# DDS_channel.net
KiCad netlist of a schematic drawn in Altium Designer
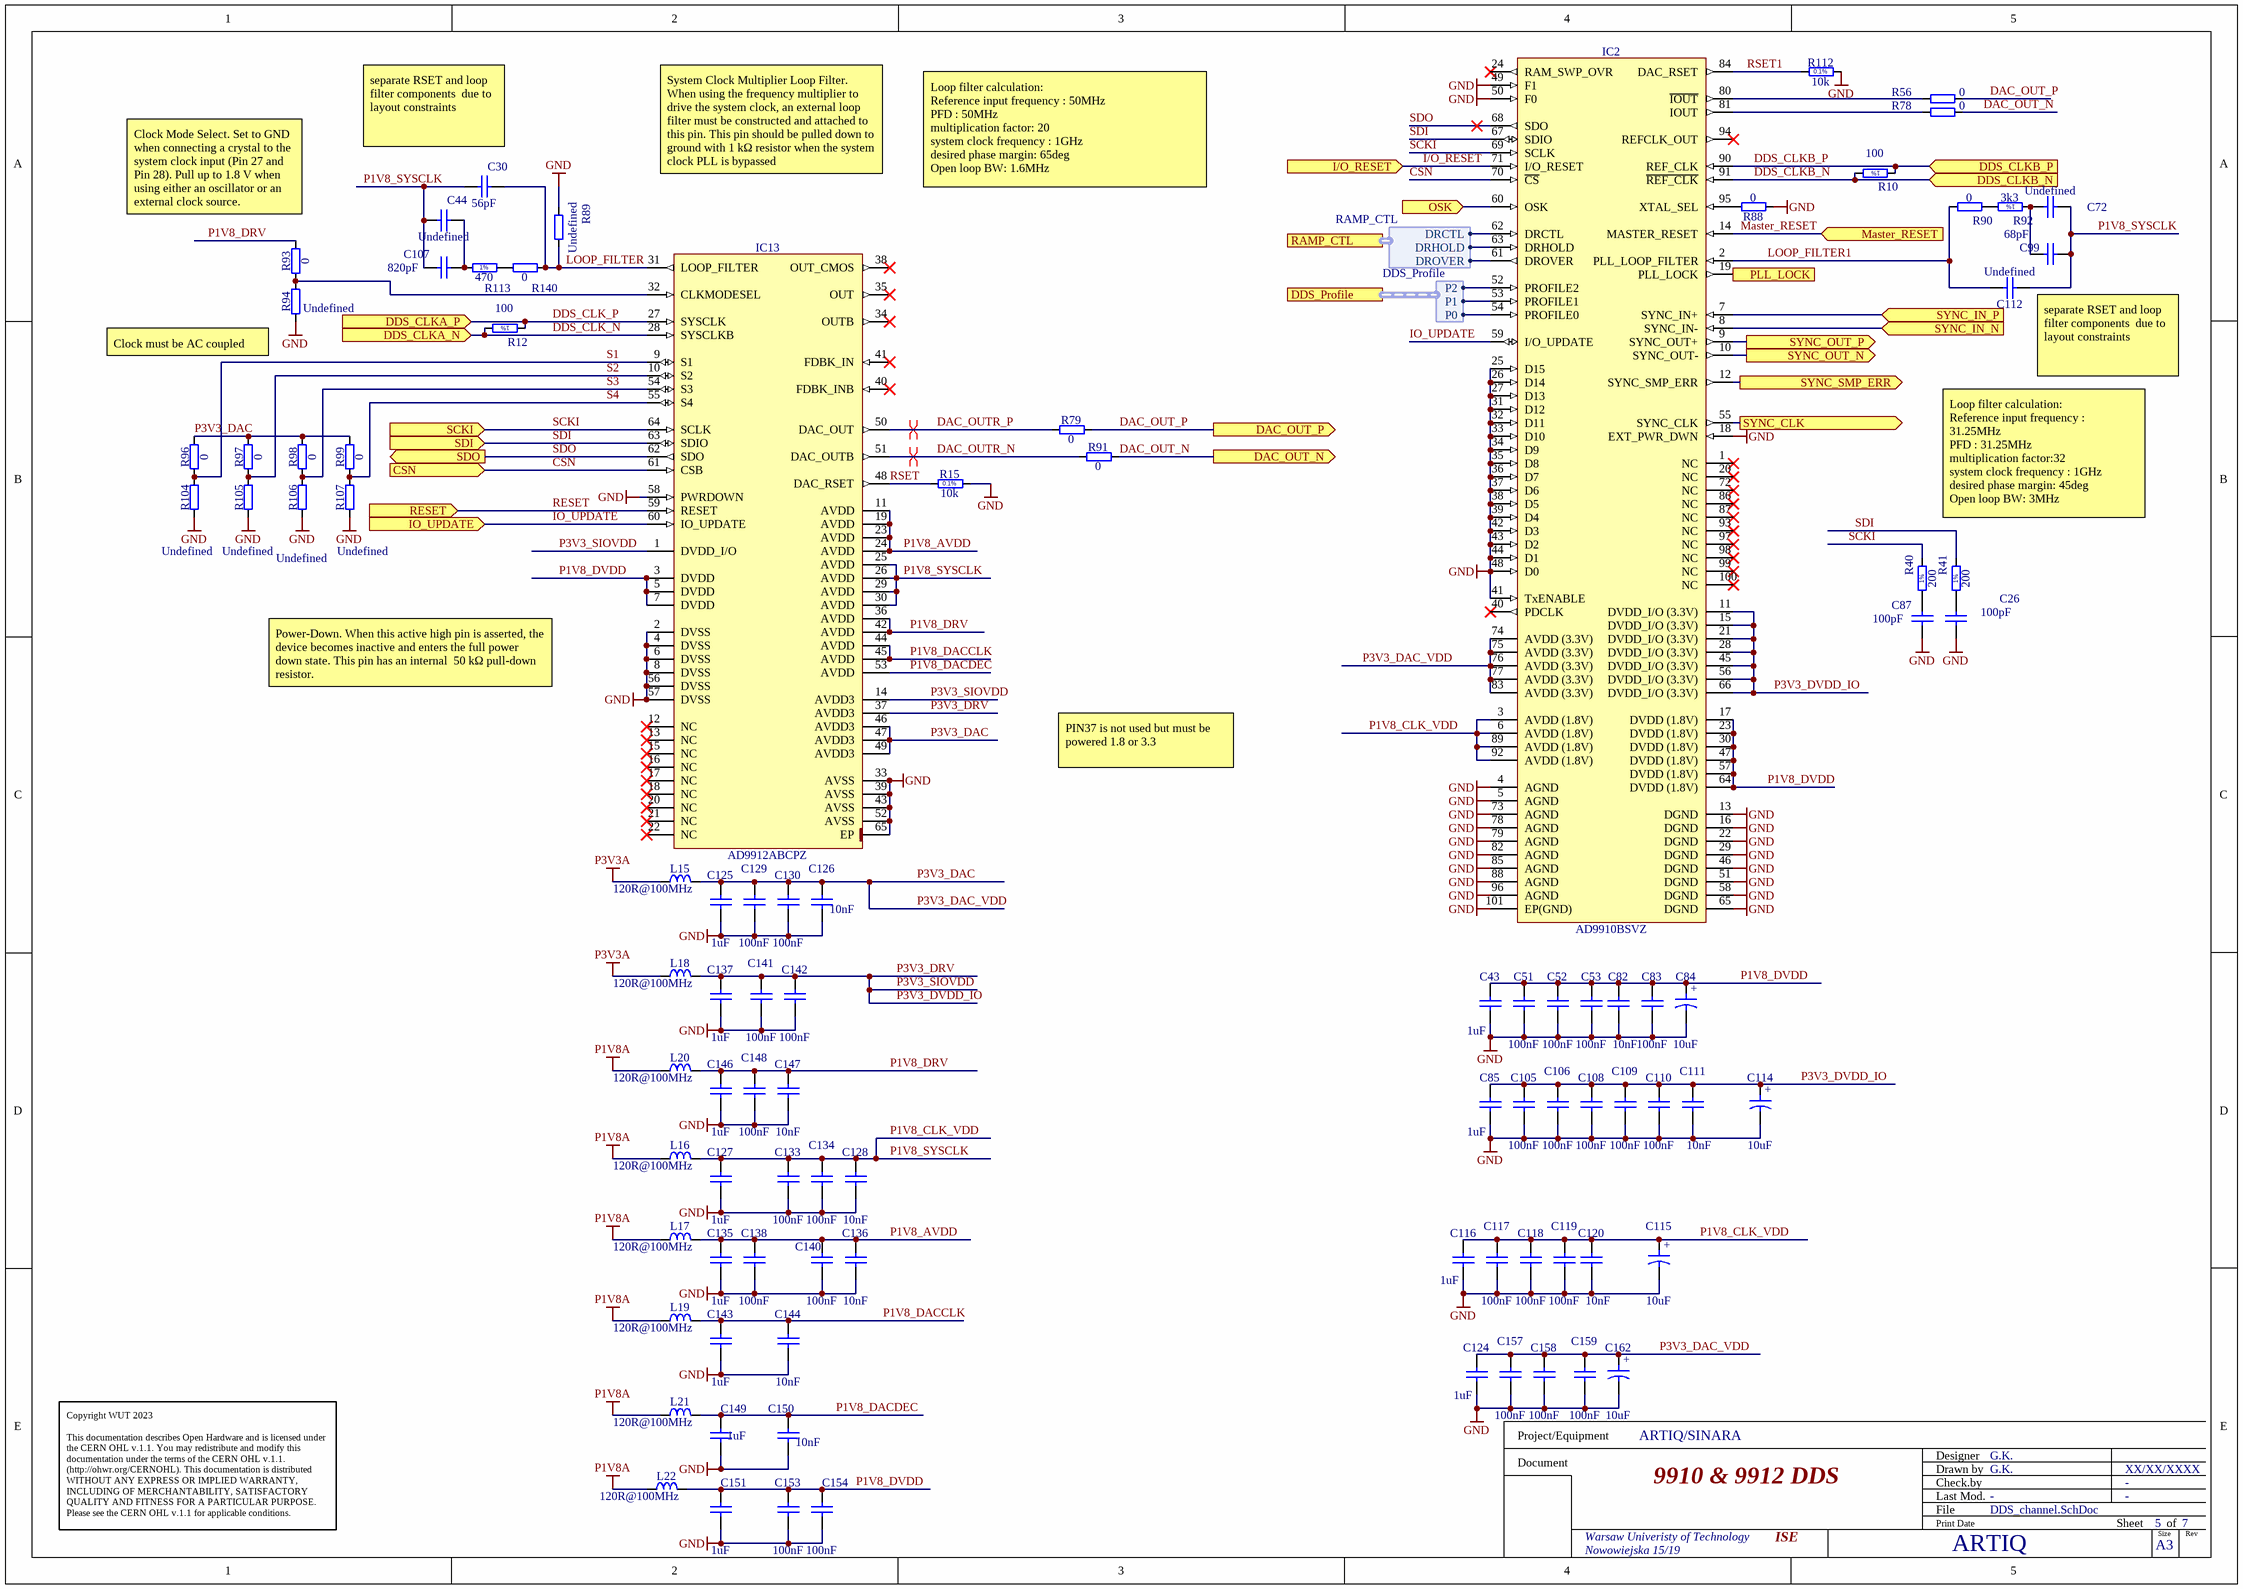
[diagram p0: DDS_channel.SchDoc]

(export (version "E")
  (design (tool "Eeschema 10.0.6"))
  (components
    (comp (ref "C26")
      (value "100pF")
      (footprint "CAPC1005X55N")
      (description "Non-polarised capacitor")
      (fields
        (field (name "PART NUMBER") "CC0402_100PF_50V_5%_C0G")
        (field (name "VOLTAGE") "50V")
        (field (name "AUTHOR") "CERN DEM JLC")
      )
      (libsource (lib "Capacitors") (part "Capacitor - non polarized"))
    )
    (comp (ref "C30")
      (value "56pF")
      (footprint "CAPC1608X87N")
      (description "Non-polarised capacitor")
      (fields
        (field (name "PART NUMBER") "CC0603_56PF_50V_5%_NP0")
        (field (name "VOLTAGE") "50V")
        (field (name "AUTHOR") "CERN DEM JLC")
      )
      (libsource (lib "Capacitors") (part "Capacitor - non polarized"))
    )
    (comp (ref "C43")
      (value "1uF")
      (footprint "CAPC1005X55N")
      (description "Non-polarised capacitor")
      (fields
        (field (name "PART NUMBER") "CC0402_1UF_16V_10%_X5R")
        (field (name "VOLTAGE") "16V")
        (field (name "AUTHOR") "CERN DEM JLC")
      )
      (libsource (lib "Capacitors") (part "Capacitor - non polarized"))
    )
    (comp (ref "C44")
      (value "Undefined")
      (footprint "CAPC1608X90N")
      (description "Non-polarised capacitor")
      (fields (field (name "PART NUMBER") "CC0603_NO-VALUE") (field (name "AUTHOR") "CERN DEM MR"))
      (libsource (lib "Capacitors") (part "Capacitor - non polarized"))
    )
    (comp (ref "C51")
      (value "100nF")
      (footprint "CAPC1005X55N")
      (description "Non-polarised capacitor")
      (fields
        (field (name "PART NUMBER") "CC0402_100NF_16V_10%_X5R")
        (field (name "VOLTAGE") "16V")
        (field (name "AUTHOR") "CERN DEM JLC")
      )
      (libsource (lib "Capacitors") (part "Capacitor - non polarized"))
    )
    (comp (ref "C52")
      (value "100nF")
      (footprint "CAPC1005X55N")
      (description "Non-polarised capacitor")
      (fields
        (field (name "PART NUMBER") "CC0402_100NF_16V_10%_X5R")
        (field (name "VOLTAGE") "16V")
        (field (name "AUTHOR") "CERN DEM JLC")
      )
      (libsource (lib "Capacitors") (part "Capacitor - non polarized"))
    )
    (comp (ref "C53")
      (value "100nF")
      (footprint "CAPC1005X55N")
      (description "Non-polarised capacitor")
      (fields
        (field (name "PART NUMBER") "CC0402_100NF_16V_10%_X5R")
        (field (name "VOLTAGE") "16V")
        (field (name "AUTHOR") "CERN DEM JLC")
      )
      (libsource (lib "Capacitors") (part "Capacitor - non polarized"))
    )
    (comp (ref "C72")
      (value "Undefined")
      (footprint "CAPC1608X90N")
      (description "Non-polarised capacitor")
      (fields (field (name "PART NUMBER") "CC0603_NO-VALUE") (field (name "AUTHOR") "CERN DEM MR"))
      (libsource (lib "Capacitors") (part "Capacitor - non polarized"))
    )
    (comp (ref "C82")
      (value "10nF")
      (footprint "CAPC1005X55N")
      (description "Non-polarised capacitor")
      (fields
        (field (name "PART NUMBER") "CC0402_10NF_16V_10%_X7R")
        (field (name "VOLTAGE") "16V")
        (field (name "AUTHOR") "CERN DEM JLC")
      )
      (libsource (lib "Capacitors") (part "Capacitor - non polarized"))
    )
    (comp (ref "C83")
      (value "100nF")
      (footprint "CAPC1005X55N")
      (description "Non-polarised capacitor")
      (fields
        (field (name "PART NUMBER") "CC0402_100NF_16V_10%_X5R")
        (field (name "VOLTAGE") "16V")
        (field (name "AUTHOR") "CERN DEM JLC")
      )
      (libsource (lib "Capacitors") (part "Capacitor - non polarized"))
    )
    (comp (ref "C84")
      (value "10uF")
      (footprint "CAPMP6032X280N")
      (description "Polarised capacitor")
      (fields
        (field (name "PART NUMBER") "CTE6032-28_10UF_25V_10%_LESR0500")
        (field (name "VOLTAGE") "25V")
        (field (name "AUTHOR") "CERN DEM JLC")
      )
      (libsource (lib "Capacitors") (part "Capacitor - polarized"))
    )
    (comp (ref "C85")
      (value "1uF")
      (footprint "CAPC1005X55N")
      (description "Non-polarised capacitor")
      (fields
        (field (name "PART NUMBER") "CC0402_1UF_16V_10%_X5R")
        (field (name "VOLTAGE") "16V")
        (field (name "AUTHOR") "CERN DEM JLC")
      )
      (libsource (lib "Capacitors") (part "Capacitor - non polarized"))
    )
    (comp (ref "C87")
      (value "100pF")
      (footprint "CAPC1005X55N")
      (description "Non-polarised capacitor")
      (fields
        (field (name "PART NUMBER") "CC0402_100PF_50V_5%_C0G")
        (field (name "VOLTAGE") "50V")
        (field (name "AUTHOR") "CERN DEM JLC")
      )
      (libsource (lib "Capacitors") (part "Capacitor - non polarized"))
    )
    (comp (ref "C99")
      (value "68pF")
      (footprint "CAPC1608X87N")
      (description "Non-polarised capacitor")
      (fields
        (field (name "PART NUMBER") "CC0603_68PF_50V_5%_NP0")
        (field (name "VOLTAGE") "50V")
        (field (name "AUTHOR") "CERN DEM JLC")
      )
      (libsource (lib "Capacitors") (part "Capacitor - non polarized"))
    )
    (comp (ref "C105")
      (value "100nF")
      (footprint "CAPC1005X55N")
      (description "Non-polarised capacitor")
      (fields
        (field (name "PART NUMBER") "CC0402_100NF_16V_10%_X5R")
        (field (name "VOLTAGE") "16V")
        (field (name "AUTHOR") "CERN DEM JLC")
      )
      (libsource (lib "Capacitors") (part "Capacitor - non polarized"))
    )
    (comp (ref "C106")
      (value "100nF")
      (footprint "CAPC1005X55N")
      (description "Non-polarised capacitor")
      (fields
        (field (name "PART NUMBER") "CC0402_100NF_16V_10%_X5R")
        (field (name "VOLTAGE") "16V")
        (field (name "AUTHOR") "CERN DEM JLC")
      )
      (libsource (lib "Capacitors") (part "Capacitor - non polarized"))
    )
    (comp (ref "C107")
      (value "820pF")
      (footprint "CAPC2012X135N")
      (description "Non-polarised capacitor")
      (fields
        (field (name "PART NUMBER") "CC0805_820PF_50V_5%_NP0")
        (field (name "VOLTAGE") "50V")
        (field (name "AUTHOR") "CERN DEM JLC")
      )
      (libsource (lib "Capacitors") (part "Capacitor - non polarized"))
    )
    (comp (ref "C108")
      (value "100nF")
      (footprint "CAPC1005X55N")
      (description "Non-polarised capacitor")
      (fields
        (field (name "PART NUMBER") "CC0402_100NF_16V_10%_X5R")
        (field (name "VOLTAGE") "16V")
        (field (name "AUTHOR") "CERN DEM JLC")
      )
      (libsource (lib "Capacitors") (part "Capacitor - non polarized"))
    )
    (comp (ref "C109")
      (value "100nF")
      (footprint "CAPC1005X55N")
      (description "Non-polarised capacitor")
      (fields
        (field (name "PART NUMBER") "CC0402_100NF_16V_10%_X5R")
        (field (name "VOLTAGE") "16V")
        (field (name "AUTHOR") "CERN DEM JLC")
      )
      (libsource (lib "Capacitors") (part "Capacitor - non polarized"))
    )
    (comp (ref "C110")
      (value "100nF")
      (footprint "CAPC1005X55N")
      (description "Non-polarised capacitor")
      (fields
        (field (name "PART NUMBER") "CC0402_100NF_16V_10%_X5R")
        (field (name "VOLTAGE") "16V")
        (field (name "AUTHOR") "CERN DEM JLC")
      )
      (libsource (lib "Capacitors") (part "Capacitor - non polarized"))
    )
    (comp (ref "C111")
      (value "10nF")
      (footprint "CAPC1005X55N")
      (description "Non-polarised capacitor")
      (fields
        (field (name "PART NUMBER") "CC0402_10NF_16V_10%_X7R")
        (field (name "VOLTAGE") "16V")
        (field (name "AUTHOR") "CERN DEM JLC")
      )
      (libsource (lib "Capacitors") (part "Capacitor - non polarized"))
    )
    (comp (ref "C112")
      (value "Undefined")
      (footprint "CAPC1608X90N")
      (description "Non-polarised capacitor")
      (fields (field (name "PART NUMBER") "CC0603_NO-VALUE") (field (name "AUTHOR") "CERN DEM MR"))
      (libsource (lib "Capacitors") (part "Capacitor - non polarized"))
    )
    (comp (ref "C114")
      (value "10uF")
      (footprint "CAPMP6032X280N")
      (description "Polarised capacitor")
      (fields
        (field (name "PART NUMBER") "CTE6032-28_10UF_25V_10%_LESR0500")
        (field (name "VOLTAGE") "25V")
        (field (name "AUTHOR") "CERN DEM JLC")
      )
      (libsource (lib "Capacitors") (part "Capacitor - polarized"))
    )
    (comp (ref "C115")
      (value "10uF")
      (footprint "CAPMP6032X280N")
      (description "Polarised capacitor")
      (fields
        (field (name "PART NUMBER") "CTE6032-28_10UF_25V_10%_LESR0500")
        (field (name "VOLTAGE") "25V")
        (field (name "AUTHOR") "CERN DEM JLC")
      )
      (libsource (lib "Capacitors") (part "Capacitor - polarized"))
    )
    (comp (ref "C116")
      (value "1uF")
      (footprint "CAPC1005X55N")
      (description "Non-polarised capacitor")
      (fields
        (field (name "PART NUMBER") "CC0402_1UF_16V_10%_X5R")
        (field (name "VOLTAGE") "16V")
        (field (name "AUTHOR") "CERN DEM JLC")
      )
      (libsource (lib "Capacitors") (part "Capacitor - non polarized"))
    )
    (comp (ref "C117")
      (value "100nF")
      (footprint "CAPC1005X55N")
      (description "Non-polarised capacitor")
      (fields
        (field (name "PART NUMBER") "CC0402_100NF_16V_10%_X5R")
        (field (name "VOLTAGE") "16V")
        (field (name "AUTHOR") "CERN DEM JLC")
      )
      (libsource (lib "Capacitors") (part "Capacitor - non polarized"))
    )
    (comp (ref "C118")
      (value "100nF")
      (footprint "CAPC1005X55N")
      (description "Non-polarised capacitor")
      (fields
        (field (name "PART NUMBER") "CC0402_100NF_16V_10%_X5R")
        (field (name "VOLTAGE") "16V")
        (field (name "AUTHOR") "CERN DEM JLC")
      )
      (libsource (lib "Capacitors") (part "Capacitor - non polarized"))
    )
    (comp (ref "C119")
      (value "100nF")
      (footprint "CAPC1005X55N")
      (description "Non-polarised capacitor")
      (fields
        (field (name "PART NUMBER") "CC0402_100NF_16V_10%_X5R")
        (field (name "VOLTAGE") "16V")
        (field (name "AUTHOR") "CERN DEM JLC")
      )
      (libsource (lib "Capacitors") (part "Capacitor - non polarized"))
    )
    (comp (ref "C120")
      (value "10nF")
      (footprint "CAPC1005X55N")
      (description "Non-polarised capacitor")
      (fields
        (field (name "PART NUMBER") "CC0402_10NF_16V_10%_X7R")
        (field (name "VOLTAGE") "16V")
        (field (name "AUTHOR") "CERN DEM JLC")
      )
      (libsource (lib "Capacitors") (part "Capacitor - non polarized"))
    )
    (comp (ref "C124")
      (value "1uF")
      (footprint "CAPC1005X55N")
      (description "Non-polarised capacitor")
      (fields
        (field (name "PART NUMBER") "CC0402_1UF_16V_10%_X5R")
        (field (name "VOLTAGE") "16V")
        (field (name "AUTHOR") "CERN DEM JLC")
      )
      (libsource (lib "Capacitors") (part "Capacitor - non polarized"))
    )
    (comp (ref "C125")
      (value "1uF")
      (footprint "CAPC1005X55N")
      (description "Non-polarised capacitor")
      (fields
        (field (name "PART NUMBER") "CC0402_1UF_16V_10%_X5R")
        (field (name "VOLTAGE") "16V")
        (field (name "AUTHOR") "CERN DEM JLC")
      )
      (libsource (lib "Capacitors") (part "Capacitor - non polarized"))
    )
    (comp (ref "C126")
      (value "10nF")
      (footprint "CAPC1005X55N")
      (description "Non-polarised capacitor")
      (fields
        (field (name "PART NUMBER") "CC0402_10NF_16V_10%_X7R")
        (field (name "VOLTAGE") "16V")
        (field (name "AUTHOR") "CERN DEM JLC")
      )
      (libsource (lib "Capacitors") (part "Capacitor - non polarized"))
    )
    (comp (ref "C127")
      (value "1uF")
      (footprint "CAPC1005X55N")
      (description "Non-polarised capacitor")
      (fields
        (field (name "PART NUMBER") "CC0402_1UF_16V_10%_X5R")
        (field (name "VOLTAGE") "16V")
        (field (name "AUTHOR") "CERN DEM JLC")
      )
      (libsource (lib "Capacitors") (part "Capacitor - non polarized"))
    )
    (comp (ref "C128")
      (value "10nF")
      (footprint "CAPC1005X55N")
      (description "Non-polarised capacitor")
      (fields
        (field (name "PART NUMBER") "CC0402_10NF_16V_10%_X7R")
        (field (name "VOLTAGE") "16V")
        (field (name "AUTHOR") "CERN DEM JLC")
      )
      (libsource (lib "Capacitors") (part "Capacitor - non polarized"))
    )
    (comp (ref "C129")
      (value "100nF")
      (footprint "CAPC1005X55N")
      (description "Non-polarised capacitor")
      (fields
        (field (name "PART NUMBER") "CC0402_100NF_16V_10%_X5R")
        (field (name "VOLTAGE") "16V")
        (field (name "AUTHOR") "CERN DEM JLC")
      )
      (libsource (lib "Capacitors") (part "Capacitor - non polarized"))
    )
    (comp (ref "C130")
      (value "100nF")
      (footprint "CAPC1005X55N")
      (description "Non-polarised capacitor")
      (fields
        (field (name "PART NUMBER") "CC0402_100NF_16V_10%_X5R")
        (field (name "VOLTAGE") "16V")
        (field (name "AUTHOR") "CERN DEM JLC")
      )
      (libsource (lib "Capacitors") (part "Capacitor - non polarized"))
    )
    (comp (ref "C133")
      (value "100nF")
      (footprint "CAPC1005X55N")
      (description "Non-polarised capacitor")
      (fields
        (field (name "PART NUMBER") "CC0402_100NF_16V_10%_X5R")
        (field (name "VOLTAGE") "16V")
        (field (name "AUTHOR") "CERN DEM JLC")
      )
      (libsource (lib "Capacitors") (part "Capacitor - non polarized"))
    )
    (comp (ref "C134")
      (value "100nF")
      (footprint "CAPC1005X55N")
      (description "Non-polarised capacitor")
      (fields
        (field (name "PART NUMBER") "CC0402_100NF_16V_10%_X5R")
        (field (name "VOLTAGE") "16V")
        (field (name "AUTHOR") "CERN DEM JLC")
      )
      (libsource (lib "Capacitors") (part "Capacitor - non polarized"))
    )
    (comp (ref "C135")
      (value "1uF")
      (footprint "CAPC1005X55N")
      (description "Non-polarised capacitor")
      (fields
        (field (name "PART NUMBER") "CC0402_1UF_16V_10%_X5R")
        (field (name "VOLTAGE") "16V")
        (field (name "AUTHOR") "CERN DEM JLC")
      )
      (libsource (lib "Capacitors") (part "Capacitor - non polarized"))
    )
    (comp (ref "C136")
      (value "10nF")
      (footprint "CAPC1005X55N")
      (description "Non-polarised capacitor")
      (fields
        (field (name "PART NUMBER") "CC0402_10NF_16V_10%_X7R")
        (field (name "VOLTAGE") "16V")
        (field (name "AUTHOR") "CERN DEM JLC")
      )
      (libsource (lib "Capacitors") (part "Capacitor - non polarized"))
    )
    (comp (ref "C137")
      (value "1uF")
      (footprint "CAPC1005X55N")
      (description "Non-polarised capacitor")
      (fields
        (field (name "PART NUMBER") "CC0402_1UF_16V_10%_X5R")
        (field (name "VOLTAGE") "16V")
        (field (name "AUTHOR") "CERN DEM JLC")
      )
      (libsource (lib "Capacitors") (part "Capacitor - non polarized"))
    )
    (comp (ref "C138")
      (value "100nF")
      (footprint "CAPC1005X55N")
      (description "Non-polarised capacitor")
      (fields
        (field (name "PART NUMBER") "CC0402_100NF_16V_10%_X5R")
        (field (name "VOLTAGE") "16V")
        (field (name "AUTHOR") "CERN DEM JLC")
      )
      (libsource (lib "Capacitors") (part "Capacitor - non polarized"))
    )
    (comp (ref "C140")
      (value "100nF")
      (footprint "CAPC1005X55N")
      (description "Non-polarised capacitor")
      (fields
        (field (name "PART NUMBER") "CC0402_100NF_16V_10%_X5R")
        (field (name "VOLTAGE") "16V")
        (field (name "AUTHOR") "CERN DEM JLC")
      )
      (libsource (lib "Capacitors") (part "Capacitor - non polarized"))
    )
    (comp (ref "C141")
      (value "100nF")
      (footprint "CAPC1005X55N")
      (description "Non-polarised capacitor")
      (fields
        (field (name "PART NUMBER") "CC0402_100NF_16V_10%_X5R")
        (field (name "VOLTAGE") "16V")
        (field (name "AUTHOR") "CERN DEM JLC")
      )
      (libsource (lib "Capacitors") (part "Capacitor - non polarized"))
    )
    (comp (ref "C142")
      (value "100nF")
      (footprint "CAPC1005X55N")
      (description "Non-polarised capacitor")
      (fields
        (field (name "PART NUMBER") "CC0402_100NF_16V_10%_X5R")
        (field (name "VOLTAGE") "16V")
        (field (name "AUTHOR") "CERN DEM JLC")
      )
      (libsource (lib "Capacitors") (part "Capacitor - non polarized"))
    )
    (comp (ref "C143")
      (value "1uF")
      (footprint "CAPC1005X55N")
      (description "Non-polarised capacitor")
      (fields
        (field (name "PART NUMBER") "CC0402_1UF_16V_10%_X5R")
        (field (name "VOLTAGE") "16V")
        (field (name "AUTHOR") "CERN DEM JLC")
      )
      (libsource (lib "Capacitors") (part "Capacitor - non polarized"))
    )
    (comp (ref "C144")
      (value "10nF")
      (footprint "CAPC1005X55N")
      (description "Non-polarised capacitor")
      (fields
        (field (name "PART NUMBER") "CC0402_10NF_16V_10%_X7R")
        (field (name "VOLTAGE") "16V")
        (field (name "AUTHOR") "CERN DEM JLC")
      )
      (libsource (lib "Capacitors") (part "Capacitor - non polarized"))
    )
    (comp (ref "C146")
      (value "1uF")
      (footprint "CAPC1005X55N")
      (description "Non-polarised capacitor")
      (fields
        (field (name "PART NUMBER") "CC0402_1UF_16V_10%_X5R")
        (field (name "VOLTAGE") "16V")
        (field (name "AUTHOR") "CERN DEM JLC")
      )
      (libsource (lib "Capacitors") (part "Capacitor - non polarized"))
    )
    (comp (ref "C147")
      (value "10nF")
      (footprint "CAPC1005X55N")
      (description "Non-polarised capacitor")
      (fields
        (field (name "PART NUMBER") "CC0402_10NF_16V_10%_X7R")
        (field (name "VOLTAGE") "16V")
        (field (name "AUTHOR") "CERN DEM JLC")
      )
      (libsource (lib "Capacitors") (part "Capacitor - non polarized"))
    )
    (comp (ref "C148")
      (value "100nF")
      (footprint "CAPC1005X55N")
      (description "Non-polarised capacitor")
      (fields
        (field (name "PART NUMBER") "CC0402_100NF_16V_10%_X5R")
        (field (name "VOLTAGE") "16V")
        (field (name "AUTHOR") "CERN DEM JLC")
      )
      (libsource (lib "Capacitors") (part "Capacitor - non polarized"))
    )
    (comp (ref "C149")
      (value "1uF")
      (footprint "CAPC1005X55N")
      (description "Non-polarised capacitor")
      (fields
        (field (name "PART NUMBER") "CC0402_1UF_16V_10%_X5R")
        (field (name "VOLTAGE") "16V")
        (field (name "AUTHOR") "CERN DEM JLC")
      )
      (libsource (lib "Capacitors") (part "Capacitor - non polarized"))
    )
    (comp (ref "C150")
      (value "10nF")
      (footprint "CAPC1005X55N")
      (description "Non-polarised capacitor")
      (fields
        (field (name "PART NUMBER") "CC0402_10NF_16V_10%_X7R")
        (field (name "VOLTAGE") "16V")
        (field (name "AUTHOR") "CERN DEM JLC")
      )
      (libsource (lib "Capacitors") (part "Capacitor - non polarized"))
    )
    (comp (ref "C151")
      (value "1uF")
      (footprint "CAPC1005X55N")
      (description "Non-polarised capacitor")
      (fields
        (field (name "PART NUMBER") "CC0402_1UF_16V_10%_X5R")
        (field (name "VOLTAGE") "16V")
        (field (name "AUTHOR") "CERN DEM JLC")
      )
      (libsource (lib "Capacitors") (part "Capacitor - non polarized"))
    )
    (comp (ref "C153")
      (value "100nF")
      (footprint "CAPC1005X55N")
      (description "Non-polarised capacitor")
      (fields
        (field (name "PART NUMBER") "CC0402_100NF_16V_10%_X5R")
        (field (name "VOLTAGE") "16V")
        (field (name "AUTHOR") "CERN DEM JLC")
      )
      (libsource (lib "Capacitors") (part "Capacitor - non polarized"))
    )
    (comp (ref "C154")
      (value "100nF")
      (footprint "CAPC1005X55N")
      (description "Non-polarised capacitor")
      (fields
        (field (name "PART NUMBER") "CC0402_100NF_16V_10%_X5R")
        (field (name "VOLTAGE") "16V")
        (field (name "AUTHOR") "CERN DEM JLC")
      )
      (libsource (lib "Capacitors") (part "Capacitor - non polarized"))
    )
    (comp (ref "C157")
      (value "100nF")
      (footprint "CAPC1005X55N")
      (description "Non-polarised capacitor")
      (fields
        (field (name "PART NUMBER") "CC0402_100NF_16V_10%_X5R")
        (field (name "VOLTAGE") "16V")
        (field (name "AUTHOR") "CERN DEM JLC")
      )
      (libsource (lib "Capacitors") (part "Capacitor - non polarized"))
    )
    (comp (ref "C158")
      (value "100nF")
      (footprint "CAPC1005X55N")
      (description "Non-polarised capacitor")
      (fields
        (field (name "PART NUMBER") "CC0402_100NF_16V_10%_X5R")
        (field (name "VOLTAGE") "16V")
        (field (name "AUTHOR") "CERN DEM JLC")
      )
      (libsource (lib "Capacitors") (part "Capacitor - non polarized"))
    )
    (comp (ref "C159")
      (value "100nF")
      (footprint "CAPC1005X55N")
      (description "Non-polarised capacitor")
      (fields
        (field (name "PART NUMBER") "CC0402_100NF_16V_10%_X5R")
        (field (name "VOLTAGE") "16V")
        (field (name "AUTHOR") "CERN DEM JLC")
      )
      (libsource (lib "Capacitors") (part "Capacitor - non polarized"))
    )
    (comp (ref "C162")
      (value "10uF")
      (footprint "CAPMP6032X280N")
      (description "Polarised capacitor")
      (fields
        (field (name "PART NUMBER") "CTE6032-28_10UF_25V_10%_LESR0500")
        (field (name "VOLTAGE") "25V")
        (field (name "AUTHOR") "CERN DEM JLC")
      )
      (libsource (lib "Capacitors") (part "Capacitor - polarized"))
    )
    (comp (ref "IC2")
      (value "AD9910BSVZ")
      (footprint "QFP50P1600X1600X120-101N-S500")
      (description "1 GSPS, 14-Bit, 3.3 V CMOS Direct Digital Synthesizer")
      (fields (field (name "MANUFACTURER") "ANALOG DEVICES") (field (name "AUTHOR") "CERN DEM JLC"))
      (libsource (lib "ICs And Semiconductors") (part "AD9910"))
    )
    (comp (ref "IC13")
      (value "AD9912ABCPZ")
      (footprint "QFN50P900X900X100-65N-S536")
      (description "1 GSPS Direct Digital Synthetizer with 14-Bit DAC")
      (fields (field (name "MANUFACTURER") "ANALOG DEVICES") (field (name "AUTHOR") "CERN DEM JLC"))
      (libsource (lib "ICs And Semiconductors") (part "AD9912"))
    )
    (comp (ref "L15")
      (value "120R@100MHz")
      (footprint "INDC1608X95N")
      (description "Inductor")
      (fields
        (field (name "PART NUMBER") "IND0603_MURATA_BLM18PG121SN1D")
        (field (name "POWER") "2A")
        (field (name "AUTHOR") "CERN DEM BC")
      )
      (libsource (lib "Inductors & Transformers") (part "Inductor"))
    )
    (comp (ref "L16")
      (value "120R@100MHz")
      (footprint "INDC1608X95N")
      (description "Inductor")
      (fields
        (field (name "PART NUMBER") "IND0603_MURATA_BLM18PG121SN1D")
        (field (name "POWER") "2A")
        (field (name "AUTHOR") "CERN DEM BC")
      )
      (libsource (lib "Inductors & Transformers") (part "Inductor"))
    )
    (comp (ref "L17")
      (value "120R@100MHz")
      (footprint "INDC1608X95N")
      (description "Inductor")
      (fields
        (field (name "PART NUMBER") "IND0603_MURATA_BLM18PG121SN1D")
        (field (name "POWER") "2A")
        (field (name "AUTHOR") "CERN DEM BC")
      )
      (libsource (lib "Inductors & Transformers") (part "Inductor"))
    )
    (comp (ref "L18")
      (value "120R@100MHz")
      (footprint "INDC1608X95N")
      (description "Inductor")
      (fields
        (field (name "PART NUMBER") "IND0603_MURATA_BLM18PG121SN1D")
        (field (name "POWER") "2A")
        (field (name "AUTHOR") "CERN DEM BC")
      )
      (libsource (lib "Inductors & Transformers") (part "Inductor"))
    )
    (comp (ref "L19")
      (value "120R@100MHz")
      (footprint "INDC1608X95N")
      (description "Inductor")
      (fields
        (field (name "PART NUMBER") "IND0603_MURATA_BLM18PG121SN1D")
        (field (name "POWER") "2A")
        (field (name "AUTHOR") "CERN DEM BC")
      )
      (libsource (lib "Inductors & Transformers") (part "Inductor"))
    )
    (comp (ref "L20")
      (value "120R@100MHz")
      (footprint "INDC1608X95N")
      (description "Inductor")
      (fields
        (field (name "PART NUMBER") "IND0603_MURATA_BLM18PG121SN1D")
        (field (name "POWER") "2A")
        (field (name "AUTHOR") "CERN DEM BC")
      )
      (libsource (lib "Inductors & Transformers") (part "Inductor"))
    )
    (comp (ref "L21")
      (value "120R@100MHz")
      (footprint "INDC1608X95N")
      (description "Inductor")
      (fields
        (field (name "PART NUMBER") "IND0603_MURATA_BLM18PG121SN1D")
        (field (name "POWER") "2A")
        (field (name "AUTHOR") "CERN DEM BC")
      )
      (libsource (lib "Inductors & Transformers") (part "Inductor"))
    )
    (comp (ref "L22")
      (value "120R@100MHz")
      (footprint "INDC1608X95N")
      (description "Inductor")
      (fields
        (field (name "PART NUMBER") "IND0603_MURATA_BLM18PG121SN1D")
        (field (name "POWER") "2A")
        (field (name "AUTHOR") "CERN DEM BC")
      )
      (libsource (lib "Inductors & Transformers") (part "Inductor"))
    )
    (comp (ref "R10")
      (value "100")
      (footprint "RESC1005X40N")
      (description "Resistor - 1%")
      (fields
        (field (name "PART NUMBER") "R0402_100R_1%_0.0625W_100PPM")
        (field (name "POWER") "0.0625W")
        (field (name "AUTHOR") "CERN DEM JLC")
      )
      (libsource (lib "Resistors") (part "Resistor - 1%"))
    )
    (comp (ref "R12")
      (value "100")
      (footprint "RESC1005X40N")
      (description "Resistor - 1%")
      (fields
        (field (name "PART NUMBER") "R0402_100R_1%_0.0625W_100PPM")
        (field (name "POWER") "0.0625W")
        (field (name "AUTHOR") "CERN DEM JLC")
      )
      (libsource (lib "Resistors") (part "Resistor - 1%"))
    )
    (comp (ref "R15")
      (value "10k")
      (footprint "RESC1005X35N")
      (description "Resistor - 0.1%")
      (fields
        (field (name "PART NUMBER") "R0402_10K_0.1%_0.063W_25PPM")
        (field (name "POWER") "0.063W")
        (field (name "AUTHOR") "CERN DEM JMW")
      )
      (libsource (lib "Resistors") (part "Resistor - 0.1%"))
    )
    (comp (ref "R40")
      (value "200")
      (footprint "RESC1005X40N")
      (description "Resistor - 1%")
      (fields
        (field (name "PART NUMBER") "R0402_200R_1%_0.0625W_100PPM")
        (field (name "POWER") "0.0625W")
        (field (name "AUTHOR") "CERN DEM JLC")
      )
      (libsource (lib "Resistors") (part "Resistor - 1%"))
    )
    (comp (ref "R41")
      (value "200")
      (footprint "RESC1005X40N")
      (description "Resistor - 1%")
      (fields
        (field (name "PART NUMBER") "R0402_200R_1%_0.0625W_100PPM")
        (field (name "POWER") "0.0625W")
        (field (name "AUTHOR") "CERN DEM JLC")
      )
      (libsource (lib "Resistors") (part "Resistor - 1%"))
    )
    (comp (ref "R56")
      (value "0")
      (footprint "RESC1005X40N")
      (description "Resistor")
      (fields
        (field (name "PART NUMBER") "R0402_0R_JUMPER")
        (field (name "MANUFACTURER") "GENERIC")
        (field (name "AUTHOR") "CERN DEM JLC")
      )
      (libsource (lib "Resistors") (part "Resistor"))
    )
    (comp (ref "R78")
      (value "0")
      (footprint "RESC1005X40N")
      (description "Resistor")
      (fields
        (field (name "PART NUMBER") "R0402_0R_JUMPER")
        (field (name "MANUFACTURER") "GENERIC")
        (field (name "AUTHOR") "CERN DEM JLC")
      )
      (libsource (lib "Resistors") (part "Resistor"))
    )
    (comp (ref "R79")
      (value "0")
      (footprint "RESC1005X40N")
      (description "Resistor")
      (fields
        (field (name "PART NUMBER") "R0402_0R_JUMPER")
        (field (name "MANUFACTURER") "GENERIC")
        (field (name "AUTHOR") "CERN DEM JLC")
      )
      (libsource (lib "Resistors") (part "Resistor"))
    )
    (comp (ref "R88")
      (value "0")
      (footprint "RESC1005X40N")
      (description "Resistor")
      (fields
        (field (name "PART NUMBER") "R0402_0R_JUMPER")
        (field (name "MANUFACTURER") "GENERIC")
        (field (name "AUTHOR") "CERN DEM JLC")
      )
      (libsource (lib "Resistors") (part "Resistor"))
    )
    (comp (ref "R89")
      (value "Undefined")
      (footprint "RESC1005X40N")
      (description "Resistor")
      (fields (field (name "PART NUMBER") "R0402_NO-VALUE") (field (name "AUTHOR") "CERN DEM JLC"))
      (libsource (lib "Resistors") (part "Resistor"))
    )
    (comp (ref "R90")
      (value "0")
      (footprint "RESC1608X55N")
      (description "Resistor")
      (fields
        (field (name "PART NUMBER") "R0603_0R_JUMPER")
        (field (name "MANUFACTURER") "GENERIC")
        (field (name "AUTHOR") "CERN DEM JLC")
      )
      (libsource (lib "Resistors") (part "Resistor"))
    )
    (comp (ref "R91")
      (value "0")
      (footprint "RESC1005X40N")
      (description "Resistor")
      (fields
        (field (name "PART NUMBER") "R0402_0R_JUMPER")
        (field (name "MANUFACTURER") "GENERIC")
        (field (name "AUTHOR") "CERN DEM JLC")
      )
      (libsource (lib "Resistors") (part "Resistor"))
    )
    (comp (ref "R92")
      (value "3k3")
      (footprint "RESC1608X55N")
      (description "Resistor - 1%")
      (fields
        (field (name "PART NUMBER") "R0603_3K3_1%_0.1W_100PPM")
        (field (name "POWER") "0.1W")
        (field (name "AUTHOR") "CERN DEM JLC")
      )
      (libsource (lib "Resistors") (part "Resistor - 1%"))
    )
    (comp (ref "R93")
      (value "0")
      (footprint "RESC1005X40N")
      (description "Resistor")
      (fields
        (field (name "PART NUMBER") "R0402_0R_JUMPER")
        (field (name "MANUFACTURER") "GENERIC")
        (field (name "AUTHOR") "CERN DEM JLC")
      )
      (libsource (lib "Resistors") (part "Resistor"))
    )
    (comp (ref "R94")
      (value "Undefined")
      (footprint "RESC1005X40N")
      (description "Resistor")
      (fields (field (name "PART NUMBER") "R0402_NO-VALUE") (field (name "AUTHOR") "CERN DEM JLC"))
      (libsource (lib "Resistors") (part "Resistor"))
    )
    (comp (ref "R96")
      (value "0")
      (footprint "RESC1005X40N")
      (description "Resistor")
      (fields
        (field (name "PART NUMBER") "R0402_0R_JUMPER")
        (field (name "MANUFACTURER") "GENERIC")
        (field (name "AUTHOR") "CERN DEM JLC")
      )
      (libsource (lib "Resistors") (part "Resistor"))
    )
    (comp (ref "R97")
      (value "0")
      (footprint "RESC1005X40N")
      (description "Resistor")
      (fields
        (field (name "PART NUMBER") "R0402_0R_JUMPER")
        (field (name "MANUFACTURER") "GENERIC")
        (field (name "AUTHOR") "CERN DEM JLC")
      )
      (libsource (lib "Resistors") (part "Resistor"))
    )
    (comp (ref "R98")
      (value "0")
      (footprint "RESC1005X40N")
      (description "Resistor")
      (fields
        (field (name "PART NUMBER") "R0402_0R_JUMPER")
        (field (name "MANUFACTURER") "GENERIC")
        (field (name "AUTHOR") "CERN DEM JLC")
      )
      (libsource (lib "Resistors") (part "Resistor"))
    )
    (comp (ref "R99")
      (value "0")
      (footprint "RESC1005X40N")
      (description "Resistor")
      (fields
        (field (name "PART NUMBER") "R0402_0R_JUMPER")
        (field (name "MANUFACTURER") "GENERIC")
        (field (name "AUTHOR") "CERN DEM JLC")
      )
      (libsource (lib "Resistors") (part "Resistor"))
    )
    (comp (ref "R104")
      (value "Undefined")
      (footprint "RESC1005X40N")
      (description "Resistor")
      (fields (field (name "PART NUMBER") "R0402_NO-VALUE") (field (name "AUTHOR") "CERN DEM JLC"))
      (libsource (lib "Resistors") (part "Resistor"))
    )
    (comp (ref "R105")
      (value "Undefined")
      (footprint "RESC1005X40N")
      (description "Resistor")
      (fields (field (name "PART NUMBER") "R0402_NO-VALUE") (field (name "AUTHOR") "CERN DEM JLC"))
      (libsource (lib "Resistors") (part "Resistor"))
    )
    (comp (ref "R106")
      (value "Undefined")
      (footprint "RESC1005X40N")
      (description "Resistor")
      (fields (field (name "PART NUMBER") "R0402_NO-VALUE") (field (name "AUTHOR") "CERN DEM JLC"))
      (libsource (lib "Resistors") (part "Resistor"))
    )
    (comp (ref "R107")
      (value "Undefined")
      (footprint "RESC1005X40N")
      (description "Resistor")
      (fields (field (name "PART NUMBER") "R0402_NO-VALUE") (field (name "AUTHOR") "CERN DEM JLC"))
      (libsource (lib "Resistors") (part "Resistor"))
    )
    (comp (ref "R112")
      (value "10k")
      (footprint "RESC1005X35N")
      (description "Resistor - 0.1%")
      (fields
        (field (name "PART NUMBER") "R0402_10K_0.1%_0.063W_25PPM")
        (field (name "POWER") "0.063W")
        (field (name "AUTHOR") "CERN DEM JMW")
      )
      (libsource (lib "Resistors") (part "Resistor - 0.1%"))
    )
    (comp (ref "R113")
      (value "470")
      (footprint "RESC1608X55N")
      (description "Resistor - 1%")
      (fields
        (field (name "PART NUMBER") "R0603_470R_1%_0.1W_100PPM")
        (field (name "POWER") "0.1W")
        (field (name "AUTHOR") "CERN DEM JLC")
      )
      (libsource (lib "Resistors") (part "Resistor - 1%"))
    )
    (comp (ref "R140")
      (value "0")
      (footprint "RESC1608X55N")
      (description "Resistor")
      (fields
        (field (name "PART NUMBER") "R0603_0R_JUMPER")
        (field (name "MANUFACTURER") "GENERIC")
        (field (name "AUTHOR") "CERN DEM JLC")
      )
      (libsource (lib "Resistors") (part "Resistor"))
    )
  )
  (nets
    (net (code "3") (name "/CSN") (class "Default")
      (node (ref "IC13") (pin "61") (pinfunction "CSB_61") (pintype "input"))
      (node (ref "IC2") (pin "70") (pinfunction "CS_70") (pintype "input"))
    )
    (net (code "4") (name "/DAC_OUTR_N") (class "Default")
      (node (ref "IC13") (pin "51") (pinfunction "DAC_OUTB_51") (pintype "output"))
      (node (ref "R91") (pin "1") (pinfunction "1_1") (pintype "passive"))
    )
    (net (code "5") (name "/DAC_OUTR_P") (class "Default")
      (node (ref "IC13") (pin "50") (pinfunction "DAC_OUT_50") (pintype "output"))
      (node (ref "R79") (pin "1") (pinfunction "1_1") (pintype "passive"))
    )
    (net (code "6") (name "/DAC_OUT_N") (class "Default")
      (node (ref "R78") (pin "2") (pinfunction "2_2") (pintype "passive"))
      (node (ref "R91") (pin "2") (pinfunction "2_2") (pintype "passive"))
    )
    (net (code "7") (name "/DAC_OUT_P") (class "Default")
      (node (ref "R56") (pin "2") (pinfunction "2_2") (pintype "passive"))
      (node (ref "R79") (pin "2") (pinfunction "2_2") (pintype "passive"))
    )
    (net (code "8") (name "/DDS_CLKB_N") (class "Default")
      (node (ref "IC2") (pin "91") (pinfunction "REF_CLK_91") (pintype "input"))
      (node (ref "R10") (pin "2") (pinfunction "2_2") (pintype "passive"))
    )
    (net (code "9") (name "/DDS_CLKB_P") (class "Default")
      (node (ref "IC2") (pin "90") (pinfunction "REF_CLK_90") (pintype "input"))
      (node (ref "R10") (pin "1") (pinfunction "1_1") (pintype "passive"))
    )
    (net (code "10") (name "/DDS_CLK_N") (class "Default")
      (node (ref "IC13") (pin "28") (pinfunction "SYSCLKB_28") (pintype "input"))
      (node (ref "R12") (pin "2") (pinfunction "2_2") (pintype "passive"))
    )
    (net (code "11") (name "/DDS_CLK_P") (class "Default")
      (node (ref "IC13") (pin "27") (pinfunction "SYSCLK_27") (pintype "input"))
      (node (ref "R12") (pin "1") (pinfunction "1_1") (pintype "passive"))
    )
    (net (code "12") (name "/DRCTL") (class "Default")
      (node (ref "IC2") (pin "62") (pinfunction "DRCTL_62") (pintype "input"))
    )
    (net (code "13") (name "/DRHOLD") (class "Default")
      (node (ref "IC2") (pin "63") (pinfunction "DRHOLD_63") (pintype "input"))
    )
    (net (code "14") (name "/DROVER") (class "Default")
      (node (ref "IC2") (pin "61") (pinfunction "DROVER_61") (pintype "output"))
    )
    (net (code "15") (name "/IO_UPDATE") (class "Default")
      (node (ref "IC13") (pin "60") (pinfunction "IO_UPDATE_60") (pintype "input"))
      (node (ref "IC2") (pin "59") (pinfunction "I/O_UPDATE_59") (pintype "bidirectional"))
    )
    (net (code "16") (name "/I{slash}O_RESET") (class "Default")
      (node (ref "IC2") (pin "71") (pinfunction "I/O_RESET_71") (pintype "input"))
    )
    (net (code "17") (name "/LOOP_FILTER") (class "Default")
      (node (ref "C30") (pin "2") (pinfunction "2_2") (pintype "passive"))
      (node (ref "IC13") (pin "31") (pinfunction "LOOP_FILTER_31") (pintype "output"))
      (node (ref "R140") (pin "2") (pinfunction "2_2") (pintype "passive"))
      (node (ref "R89") (pin "1") (pinfunction "1_1") (pintype "passive"))
    )
    (net (code "18") (name "/LOOP_FILTER1") (class "Default")
      (node (ref "C112") (pin "2") (pinfunction "2_2") (pintype "passive"))
      (node (ref "IC2") (pin "2") (pinfunction "PLL_LOOP_FILTER_2") (pintype "input"))
      (node (ref "R90") (pin "2") (pinfunction "2_2") (pintype "passive"))
    )
    (net (code "19") (name "/Master_RESET") (class "Default")
      (node (ref "IC2") (pin "14") (pinfunction "MASTER_RESET_14") (pintype "input"))
    )
    (net (code "20") (name "/OSK") (class "Default")
      (node (ref "IC2") (pin "60") (pinfunction "OSK_60") (pintype "input"))
    )
    (net (code "21") (name "/P0") (class "Default")
      (node (ref "IC2") (pin "54") (pinfunction "PROFILE0_54") (pintype "input"))
    )
    (net (code "22") (name "/P1") (class "Default")
      (node (ref "IC2") (pin "53") (pinfunction "PROFILE1_53") (pintype "input"))
    )
    (net (code "23") (name "/P1V8_AVDD") (class "Default")
      (node (ref "C135") (pin "2") (pinfunction "2_2") (pintype "passive"))
      (node (ref "C136") (pin "2") (pinfunction "2_2") (pintype "passive"))
      (node (ref "C138") (pin "2") (pinfunction "2_2") (pintype "passive"))
      (node (ref "C140") (pin "2") (pinfunction "2_2") (pintype "passive"))
      (node (ref "IC13") (pin "11") (pinfunction "AVDD_11") (pintype "power_in"))
      (node (ref "IC13") (pin "19") (pinfunction "AVDD_19") (pintype "power_in"))
      (node (ref "IC13") (pin "23") (pinfunction "AVDD_23") (pintype "power_in"))
      (node (ref "IC13") (pin "24") (pinfunction "AVDD_24") (pintype "power_in"))
      (node (ref "L17") (pin "1") (pinfunction "1_1") (pintype "passive"))
    )
    (net (code "24") (name "/P1V8_CLK_VDD") (class "Default")
      (node (ref "C107") (pin "1") (pinfunction "1_1") (pintype "passive"))
      (node (ref "C112") (pin "1") (pinfunction "1_1") (pintype "passive"))
      (node (ref "C115") (pin "1") (pinfunction "1_1") (pintype "passive"))
      (node (ref "C116") (pin "2") (pinfunction "2_2") (pintype "passive"))
      (node (ref "C117") (pin "2") (pinfunction "2_2") (pintype "passive"))
      (node (ref "C118") (pin "2") (pinfunction "2_2") (pintype "passive"))
      (node (ref "C119") (pin "2") (pinfunction "2_2") (pintype "passive"))
      (node (ref "C120") (pin "2") (pinfunction "2_2") (pintype "passive"))
      (node (ref "C127") (pin "2") (pinfunction "2_2") (pintype "passive"))
      (node (ref "C128") (pin "2") (pinfunction "2_2") (pintype "passive"))
      (node (ref "C133") (pin "2") (pinfunction "2_2") (pintype "passive"))
      (node (ref "C134") (pin "2") (pinfunction "2_2") (pintype "passive"))
      (node (ref "C30") (pin "1") (pinfunction "1_1") (pintype "passive"))
      (node (ref "C44") (pin "1") (pinfunction "1_1") (pintype "passive"))
      (node (ref "C72") (pin "1") (pinfunction "1_1") (pintype "passive"))
      (node (ref "C99") (pin "1") (pinfunction "1_1") (pintype "passive"))
      (node (ref "IC13") (pin "25") (pinfunction "AVDD_25") (pintype "power_in"))
      (node (ref "IC13") (pin "26") (pinfunction "AVDD_26") (pintype "power_in"))
      (node (ref "IC13") (pin "29") (pinfunction "AVDD_29") (pintype "power_in"))
      (node (ref "IC13") (pin "30") (pinfunction "AVDD_30") (pintype "power_in"))
      (node (ref "IC2") (pin "3") (pinfunction "AVDD_(1.8V)_3") (pintype "power_in"))
      (node (ref "IC2") (pin "6") (pinfunction "AVDD_(1.8V)_6") (pintype "power_in"))
      (node (ref "IC2") (pin "89") (pinfunction "AVDD_(1.8V)_89") (pintype "power_in"))
      (node (ref "IC2") (pin "92") (pinfunction "AVDD_(1.8V)_92") (pintype "power_in"))
      (node (ref "L16") (pin "1") (pinfunction "1_1") (pintype "passive"))
    )
    (net (code "25") (name "/P1V8_DACCLK") (class "Default")
      (node (ref "C143") (pin "2") (pinfunction "2_2") (pintype "passive"))
      (node (ref "C144") (pin "2") (pinfunction "2_2") (pintype "passive"))
      (node (ref "IC13") (pin "44") (pinfunction "AVDD_44") (pintype "power_in"))
      (node (ref "IC13") (pin "45") (pinfunction "AVDD_45") (pintype "power_in"))
      (node (ref "L19") (pin "1") (pinfunction "1_1") (pintype "passive"))
    )
    (net (code "26") (name "/P1V8_DACDEC") (class "Default")
      (node (ref "C149") (pin "2") (pinfunction "2_2") (pintype "passive"))
      (node (ref "C150") (pin "2") (pinfunction "2_2") (pintype "passive"))
      (node (ref "IC13") (pin "53") (pinfunction "AVDD_53") (pintype "power_in"))
      (node (ref "L21") (pin "1") (pinfunction "1_1") (pintype "passive"))
    )
    (net (code "27") (name "/P1V8_DRV") (class "Default")
      (node (ref "C146") (pin "2") (pinfunction "2_2") (pintype "passive"))
      (node (ref "C147") (pin "2") (pinfunction "2_2") (pintype "passive"))
      (node (ref "C148") (pin "2") (pinfunction "2_2") (pintype "passive"))
      (node (ref "IC13") (pin "36") (pinfunction "AVDD_36") (pintype "power_in"))
      (node (ref "IC13") (pin "42") (pinfunction "AVDD_42") (pintype "power_in"))
      (node (ref "L20") (pin "1") (pinfunction "1_1") (pintype "passive"))
      (node (ref "R93") (pin "2") (pinfunction "2_2") (pintype "passive"))
    )
    (net (code "28") (name "/P1V8_DVDD") (class "Default")
      (node (ref "C151") (pin "2") (pinfunction "2_2") (pintype "passive"))
      (node (ref "C153") (pin "2") (pinfunction "2_2") (pintype "passive"))
      (node (ref "C154") (pin "2") (pinfunction "2_2") (pintype "passive"))
      (node (ref "C43") (pin "2") (pinfunction "2_2") (pintype "passive"))
      (node (ref "C51") (pin "2") (pinfunction "2_2") (pintype "passive"))
      (node (ref "C52") (pin "2") (pinfunction "2_2") (pintype "passive"))
      (node (ref "C53") (pin "2") (pinfunction "2_2") (pintype "passive"))
      (node (ref "C82") (pin "2") (pinfunction "2_2") (pintype "passive"))
      (node (ref "C83") (pin "2") (pinfunction "2_2") (pintype "passive"))
      (node (ref "C84") (pin "1") (pinfunction "1_1") (pintype "passive"))
      (node (ref "IC13") (pin "3") (pinfunction "DVDD_3") (pintype "power_in"))
      (node (ref "IC13") (pin "5") (pinfunction "DVDD_5") (pintype "power_in"))
      (node (ref "IC13") (pin "7") (pinfunction "DVDD_7") (pintype "power_in"))
      (node (ref "IC2") (pin "17") (pinfunction "DVDD_(1.8V)_17") (pintype "power_in"))
      (node (ref "IC2") (pin "23") (pinfunction "DVDD_(1.8V)_23") (pintype "power_in"))
      (node (ref "IC2") (pin "30") (pinfunction "DVDD_(1.8V)_30") (pintype "power_in"))
      (node (ref "IC2") (pin "47") (pinfunction "DVDD_(1.8V)_47") (pintype "power_in"))
      (node (ref "IC2") (pin "57") (pinfunction "DVDD_(1.8V)_57") (pintype "power_in"))
      (node (ref "IC2") (pin "64") (pinfunction "DVDD_(1.8V)_64") (pintype "power_in"))
      (node (ref "L22") (pin "1") (pinfunction "1_1") (pintype "passive"))
    )
    (net (code "29") (name "/P2") (class "Default")
      (node (ref "IC2") (pin "52") (pinfunction "PROFILE2_52") (pintype "input"))
    )
    (net (code "30") (name "/P3V3_DAC") (class "Default")
      (node (ref "C124") (pin "2") (pinfunction "2_2") (pintype "passive"))
      (node (ref "C125") (pin "2") (pinfunction "2_2") (pintype "passive"))
      (node (ref "C126") (pin "2") (pinfunction "2_2") (pintype "passive"))
      (node (ref "C129") (pin "2") (pinfunction "2_2") (pintype "passive"))
      (node (ref "C130") (pin "2") (pinfunction "2_2") (pintype "passive"))
      (node (ref "C157") (pin "2") (pinfunction "2_2") (pintype "passive"))
      (node (ref "C158") (pin "2") (pinfunction "2_2") (pintype "passive"))
      (node (ref "C159") (pin "2") (pinfunction "2_2") (pintype "passive"))
      (node (ref "C162") (pin "1") (pinfunction "1_1") (pintype "passive"))
      (node (ref "IC13") (pin "46") (pinfunction "AVDD3_46") (pintype "power_in"))
      (node (ref "IC13") (pin "47") (pinfunction "AVDD3_47") (pintype "power_in"))
      (node (ref "IC13") (pin "49") (pinfunction "AVDD3_49") (pintype "power_in"))
      (node (ref "IC2") (pin "74") (pinfunction "AVDD_(3.3V)_74") (pintype "power_in"))
      (node (ref "IC2") (pin "75") (pinfunction "AVDD_(3.3V)_75") (pintype "power_in"))
      (node (ref "IC2") (pin "76") (pinfunction "AVDD_(3.3V)_76") (pintype "power_in"))
      (node (ref "IC2") (pin "77") (pinfunction "AVDD_(3.3V)_77") (pintype "power_in"))
      (node (ref "IC2") (pin "83") (pinfunction "AVDD_(3.3V)_83") (pintype "power_in"))
      (node (ref "L15") (pin "1") (pinfunction "1_1") (pintype "passive"))
      (node (ref "R96") (pin "2") (pinfunction "2_2") (pintype "passive"))
      (node (ref "R97") (pin "2") (pinfunction "2_2") (pintype "passive"))
      (node (ref "R98") (pin "2") (pinfunction "2_2") (pintype "passive"))
      (node (ref "R99") (pin "2") (pinfunction "2_2") (pintype "passive"))
    )
    (net (code "31") (name "/P3V3_DRV") (class "Default")
      (node (ref "C105") (pin "2") (pinfunction "2_2") (pintype "passive"))
      (node (ref "C106") (pin "2") (pinfunction "2_2") (pintype "passive"))
      (node (ref "C108") (pin "2") (pinfunction "2_2") (pintype "passive"))
      (node (ref "C109") (pin "2") (pinfunction "2_2") (pintype "passive"))
      (node (ref "C110") (pin "2") (pinfunction "2_2") (pintype "passive"))
      (node (ref "C111") (pin "2") (pinfunction "2_2") (pintype "passive"))
      (node (ref "C114") (pin "1") (pinfunction "1_1") (pintype "passive"))
      (node (ref "C137") (pin "2") (pinfunction "2_2") (pintype "passive"))
      (node (ref "C141") (pin "2") (pinfunction "2_2") (pintype "passive"))
      (node (ref "C142") (pin "2") (pinfunction "2_2") (pintype "passive"))
      (node (ref "C85") (pin "2") (pinfunction "2_2") (pintype "passive"))
      (node (ref "IC13") (pin "1") (pinfunction "DVDD_I/O_1") (pintype "power_in"))
      (node (ref "IC13") (pin "14") (pinfunction "AVDD3_14") (pintype "power_in"))
      (node (ref "IC13") (pin "37") (pinfunction "AVDD3_37") (pintype "power_in"))
      (node (ref "IC2") (pin "11") (pinfunction "DVDD_I/O_(3.3V)_11") (pintype "power_in"))
      (node (ref "IC2") (pin "15") (pinfunction "DVDD_I/O_(3.3V)_15") (pintype "power_in"))
      (node (ref "IC2") (pin "21") (pinfunction "DVDD_I/O_(3.3V)_21") (pintype "power_in"))
      (node (ref "IC2") (pin "28") (pinfunction "DVDD_I/O_(3.3V)_28") (pintype "power_in"))
      (node (ref "IC2") (pin "45") (pinfunction "DVDD_I/O_(3.3V)_45") (pintype "power_in"))
      (node (ref "IC2") (pin "56") (pinfunction "DVDD_I/O_(3.3V)_56") (pintype "power_in"))
      (node (ref "IC2") (pin "66") (pinfunction "DVDD_I/O_(3.3V)_66") (pintype "power_in"))
      (node (ref "L18") (pin "1") (pinfunction "1_1") (pintype "passive"))
    )
    (net (code "32") (name "/PLL_LOCK") (class "Default")
      (node (ref "IC2") (pin "19") (pinfunction "PLL_LOCK_19") (pintype "output"))
    )
    (net (code "33") (name "/RESET") (class "Default")
      (node (ref "IC13") (pin "59") (pinfunction "RESET_59") (pintype "input"))
    )
    (net (code "34") (name "/RSET") (class "Default")
      (node (ref "IC13") (pin "48") (pinfunction "DAC_RSET_48") (pintype "output"))
      (node (ref "R15") (pin "1") (pinfunction "1_1") (pintype "passive"))
    )
    (net (code "35") (name "/RSET1") (class "Default")
      (node (ref "IC2") (pin "84") (pinfunction "DAC_RSET_84") (pintype "output"))
      (node (ref "R112") (pin "1") (pinfunction "1_1") (pintype "passive"))
    )
    (net (code "36") (name "/S1") (class "Default")
      (node (ref "IC13") (pin "9") (pinfunction "S1_9") (pintype "bidirectional"))
      (node (ref "R104") (pin "2") (pinfunction "2_2") (pintype "passive"))
      (node (ref "R96") (pin "1") (pinfunction "1_1") (pintype "passive"))
    )
    (net (code "37") (name "/S2") (class "Default")
      (node (ref "IC13") (pin "10") (pinfunction "S2_10") (pintype "bidirectional"))
      (node (ref "R105") (pin "2") (pinfunction "2_2") (pintype "passive"))
      (node (ref "R97") (pin "1") (pinfunction "1_1") (pintype "passive"))
    )
    (net (code "38") (name "/S3") (class "Default")
      (node (ref "IC13") (pin "54") (pinfunction "S3_54") (pintype "bidirectional"))
      (node (ref "R106") (pin "2") (pinfunction "2_2") (pintype "passive"))
      (node (ref "R98") (pin "1") (pinfunction "1_1") (pintype "passive"))
    )
    (net (code "39") (name "/S4") (class "Default")
      (node (ref "IC13") (pin "55") (pinfunction "S4_55") (pintype "bidirectional"))
      (node (ref "R107") (pin "2") (pinfunction "2_2") (pintype "passive"))
      (node (ref "R99") (pin "1") (pinfunction "1_1") (pintype "passive"))
    )
    (net (code "40") (name "/SCKI") (class "Default")
      (node (ref "IC13") (pin "64") (pinfunction "SCLK_64") (pintype "input"))
      (node (ref "IC2") (pin "69") (pinfunction "SCLK_69") (pintype "input"))
      (node (ref "R40") (pin "2") (pinfunction "2_2") (pintype "passive"))
    )
    (net (code "41") (name "/SDI") (class "Default")
      (node (ref "IC13") (pin "63") (pinfunction "SDIO_63") (pintype "bidirectional"))
      (node (ref "IC2") (pin "67") (pinfunction "SDIO_67") (pintype "bidirectional"))
      (node (ref "R41") (pin "2") (pinfunction "2_2") (pintype "passive"))
    )
    (net (code "42") (name "/SDO") (class "Default")
      (node (ref "IC13") (pin "62") (pinfunction "SDO_62") (pintype "output"))
      (node (ref "IC2") (pin "68") (pinfunction "SDO_68") (pintype "output"))
    )
    (net (code "43") (name "/SYNC_CLK") (class "Default")
      (node (ref "IC2") (pin "55") (pinfunction "SYNC_CLK_55") (pintype "output"))
    )
    (net (code "44") (name "/SYNC_IN_N") (class "Default")
      (node (ref "IC2") (pin "8") (pinfunction "SYNC_IN-_8") (pintype "input"))
    )
    (net (code "45") (name "/SYNC_IN_P") (class "Default")
      (node (ref "IC2") (pin "7") (pinfunction "SYNC_IN+_7") (pintype "input"))
    )
    (net (code "46") (name "/SYNC_OUT_N") (class "Default")
      (node (ref "IC2") (pin "10") (pinfunction "SYNC_OUT-_10") (pintype "output"))
    )
    (net (code "47") (name "/SYNC_OUT_P") (class "Default")
      (node (ref "IC2") (pin "9") (pinfunction "SYNC_OUT+_9") (pintype "output"))
    )
    (net (code "48") (name "/SYNC_SMP_ERR") (class "Default")
      (node (ref "IC2") (pin "12") (pinfunction "SYNC_SMP_ERR_12") (pintype "output"))
    )
    (net (code "51") (name "GND") (class "Default")
      (node (ref "C105") (pin "1") (pinfunction "1_1") (pintype "passive"))
      (node (ref "C106") (pin "1") (pinfunction "1_1") (pintype "passive"))
      (node (ref "C108") (pin "1") (pinfunction "1_1") (pintype "passive"))
      (node (ref "C109") (pin "1") (pinfunction "1_1") (pintype "passive"))
      (node (ref "C110") (pin "1") (pinfunction "1_1") (pintype "passive"))
      (node (ref "C111") (pin "1") (pinfunction "1_1") (pintype "passive"))
      (node (ref "C114") (pin "2") (pinfunction "2_2") (pintype "passive"))
      (node (ref "C115") (pin "2") (pinfunction "2_2") (pintype "passive"))
      (node (ref "C116") (pin "1") (pinfunction "1_1") (pintype "passive"))
      (node (ref "C117") (pin "1") (pinfunction "1_1") (pintype "passive"))
      (node (ref "C118") (pin "1") (pinfunction "1_1") (pintype "passive"))
      (node (ref "C119") (pin "1") (pinfunction "1_1") (pintype "passive"))
      (node (ref "C120") (pin "1") (pinfunction "1_1") (pintype "passive"))
      (node (ref "C124") (pin "1") (pinfunction "1_1") (pintype "passive"))
      (node (ref "C125") (pin "1") (pinfunction "1_1") (pintype "passive"))
      (node (ref "C126") (pin "1") (pinfunction "1_1") (pintype "passive"))
      (node (ref "C127") (pin "1") (pinfunction "1_1") (pintype "passive"))
      (node (ref "C128") (pin "1") (pinfunction "1_1") (pintype "passive"))
      (node (ref "C129") (pin "1") (pinfunction "1_1") (pintype "passive"))
      (node (ref "C130") (pin "1") (pinfunction "1_1") (pintype "passive"))
      (node (ref "C133") (pin "1") (pinfunction "1_1") (pintype "passive"))
      (node (ref "C134") (pin "1") (pinfunction "1_1") (pintype "passive"))
      (node (ref "C135") (pin "1") (pinfunction "1_1") (pintype "passive"))
      (node (ref "C136") (pin "1") (pinfunction "1_1") (pintype "passive"))
      (node (ref "C137") (pin "1") (pinfunction "1_1") (pintype "passive"))
      (node (ref "C138") (pin "1") (pinfunction "1_1") (pintype "passive"))
      (node (ref "C140") (pin "1") (pinfunction "1_1") (pintype "passive"))
      (node (ref "C141") (pin "1") (pinfunction "1_1") (pintype "passive"))
      (node (ref "C142") (pin "1") (pinfunction "1_1") (pintype "passive"))
      (node (ref "C143") (pin "1") (pinfunction "1_1") (pintype "passive"))
      (node (ref "C144") (pin "1") (pinfunction "1_1") (pintype "passive"))
      (node (ref "C146") (pin "1") (pinfunction "1_1") (pintype "passive"))
      (node (ref "C147") (pin "1") (pinfunction "1_1") (pintype "passive"))
      (node (ref "C148") (pin "1") (pinfunction "1_1") (pintype "passive"))
      (node (ref "C149") (pin "1") (pinfunction "1_1") (pintype "passive"))
      (node (ref "C150") (pin "1") (pinfunction "1_1") (pintype "passive"))
      (node (ref "C151") (pin "1") (pinfunction "1_1") (pintype "passive"))
      (node (ref "C153") (pin "1") (pinfunction "1_1") (pintype "passive"))
      (node (ref "C154") (pin "1") (pinfunction "1_1") (pintype "passive"))
      (node (ref "C157") (pin "1") (pinfunction "1_1") (pintype "passive"))
      (node (ref "C158") (pin "1") (pinfunction "1_1") (pintype "passive"))
      (node (ref "C159") (pin "1") (pinfunction "1_1") (pintype "passive"))
      (node (ref "C162") (pin "2") (pinfunction "2_2") (pintype "passive"))
      (node (ref "C26") (pin "1") (pinfunction "1_1") (pintype "passive"))
      (node (ref "C43") (pin "1") (pinfunction "1_1") (pintype "passive"))
      (node (ref "C51") (pin "1") (pinfunction "1_1") (pintype "passive"))
      (node (ref "C52") (pin "1") (pinfunction "1_1") (pintype "passive"))
      (node (ref "C53") (pin "1") (pinfunction "1_1") (pintype "passive"))
      (node (ref "C82") (pin "1") (pinfunction "1_1") (pintype "passive"))
      (node (ref "C83") (pin "1") (pinfunction "1_1") (pintype "passive"))
      (node (ref "C84") (pin "2") (pinfunction "2_2") (pintype "passive"))
      (node (ref "C85") (pin "1") (pinfunction "1_1") (pintype "passive"))
      (node (ref "C87") (pin "1") (pinfunction "1_1") (pintype "passive"))
      (node (ref "IC13") (pin "2") (pinfunction "DVSS_2") (pintype "power_in"))
      (node (ref "IC13") (pin "33") (pinfunction "AVSS_33") (pintype "power_in"))
      (node (ref "IC13") (pin "39") (pinfunction "AVSS_39") (pintype "power_in"))
      (node (ref "IC13") (pin "4") (pinfunction "DVSS_4") (pintype "power_in"))
      (node (ref "IC13") (pin "43") (pinfunction "AVSS_43") (pintype "power_in"))
      (node (ref "IC13") (pin "52") (pinfunction "AVSS_52") (pintype "power_in"))
      (node (ref "IC13") (pin "56") (pinfunction "DVSS_56") (pintype "power_in"))
      (node (ref "IC13") (pin "57") (pinfunction "DVSS_57") (pintype "power_in"))
      (node (ref "IC13") (pin "58") (pinfunction "PWRDOWN_58") (pintype "input"))
      (node (ref "IC13") (pin "6") (pinfunction "DVSS_6") (pintype "power_in"))
      (node (ref "IC13") (pin "65") (pinfunction "EP_65") (pintype "power_in"))
      (node (ref "IC13") (pin "8") (pinfunction "DVSS_8") (pintype "power_in"))
      (node (ref "IC2") (pin "101") (pinfunction "EP(GND)_101") (pintype "power_in"))
      (node (ref "IC2") (pin "13") (pinfunction "DGND_13") (pintype "power_in"))
      (node (ref "IC2") (pin "16") (pinfunction "DGND_16") (pintype "power_in"))
      (node (ref "IC2") (pin "18") (pinfunction "EXT_PWR_DWN_18") (pintype "input"))
      (node (ref "IC2") (pin "22") (pinfunction "DGND_22") (pintype "power_in"))
      (node (ref "IC2") (pin "25") (pinfunction "D15_25") (pintype "input"))
      (node (ref "IC2") (pin "26") (pinfunction "D14_26") (pintype "input"))
      (node (ref "IC2") (pin "27") (pinfunction "D13_27") (pintype "input"))
      (node (ref "IC2") (pin "29") (pinfunction "DGND_29") (pintype "power_in"))
      (node (ref "IC2") (pin "31") (pinfunction "D12_31") (pintype "input"))
      (node (ref "IC2") (pin "32") (pinfunction "D11_32") (pintype "input"))
      (node (ref "IC2") (pin "33") (pinfunction "D10_33") (pintype "input"))
      (node (ref "IC2") (pin "34") (pinfunction "D9_34") (pintype "input"))
      (node (ref "IC2") (pin "35") (pinfunction "D8_35") (pintype "input"))
      (node (ref "IC2") (pin "36") (pinfunction "D7_36") (pintype "input"))
      (node (ref "IC2") (pin "37") (pinfunction "D6_37") (pintype "input"))
      (node (ref "IC2") (pin "38") (pinfunction "D5_38") (pintype "input"))
      (node (ref "IC2") (pin "39") (pinfunction "D4_39") (pintype "input"))
      (node (ref "IC2") (pin "4") (pinfunction "AGND_4") (pintype "power_in"))
      (node (ref "IC2") (pin "41") (pinfunction "TxENABLE_41") (pintype "input"))
      (node (ref "IC2") (pin "42") (pinfunction "D3_42") (pintype "input"))
      (node (ref "IC2") (pin "43") (pinfunction "D2_43") (pintype "input"))
      (node (ref "IC2") (pin "44") (pinfunction "D1_44") (pintype "input"))
      (node (ref "IC2") (pin "46") (pinfunction "DGND_46") (pintype "power_in"))
      (node (ref "IC2") (pin "48") (pinfunction "D0_48") (pintype "input"))
      (node (ref "IC2") (pin "49") (pinfunction "F1_49") (pintype "input"))
      (node (ref "IC2") (pin "5") (pinfunction "AGND_5") (pintype "power_in"))
      (node (ref "IC2") (pin "50") (pinfunction "F0_50") (pintype "input"))
      (node (ref "IC2") (pin "51") (pinfunction "DGND_51") (pintype "power_in"))
      (node (ref "IC2") (pin "58") (pinfunction "DGND_58") (pintype "power_in"))
      (node (ref "IC2") (pin "65") (pinfunction "DGND_65") (pintype "power_in"))
      (node (ref "IC2") (pin "73") (pinfunction "AGND_73") (pintype "power_in"))
      (node (ref "IC2") (pin "78") (pinfunction "AGND_78") (pintype "power_in"))
      (node (ref "IC2") (pin "79") (pinfunction "AGND_79") (pintype "power_in"))
      (node (ref "IC2") (pin "82") (pinfunction "AGND_82") (pintype "power_in"))
      (node (ref "IC2") (pin "85") (pinfunction "AGND_85") (pintype "power_in"))
      (node (ref "IC2") (pin "88") (pinfunction "AGND_88") (pintype "power_in"))
      (node (ref "IC2") (pin "96") (pinfunction "AGND_96") (pintype "power_in"))
      (node (ref "R104") (pin "1") (pinfunction "1_1") (pintype "passive"))
      (node (ref "R105") (pin "1") (pinfunction "1_1") (pintype "passive"))
      (node (ref "R106") (pin "1") (pinfunction "1_1") (pintype "passive"))
      (node (ref "R107") (pin "1") (pinfunction "1_1") (pintype "passive"))
      (node (ref "R112") (pin "2") (pinfunction "2_2") (pintype "passive"))
      (node (ref "R15") (pin "2") (pinfunction "2_2") (pintype "passive"))
      (node (ref "R88") (pin "1") (pinfunction "1_1") (pintype "passive"))
      (node (ref "R89") (pin "2") (pinfunction "2_2") (pintype "passive"))
      (node (ref "R94") (pin "1") (pinfunction "1_1") (pintype "passive"))
    )
    (net (code "52") (name "Net-(C26-Pad2)") (class "Default")
      (node (ref "C26") (pin "2") (pinfunction "2_2") (pintype "passive"))
      (node (ref "R41") (pin "1") (pinfunction "1_1") (pintype "passive"))
    )
    (net (code "53") (name "Net-(C72-Pad2)") (class "Default")
      (node (ref "C72") (pin "2") (pinfunction "2_2") (pintype "passive"))
      (node (ref "C99") (pin "2") (pinfunction "2_2") (pintype "passive"))
      (node (ref "R92") (pin "1") (pinfunction "1_1") (pintype "passive"))
    )
    (net (code "54") (name "Net-(C87-Pad2)") (class "Default")
      (node (ref "C87") (pin "2") (pinfunction "2_2") (pintype "passive"))
      (node (ref "R40") (pin "1") (pinfunction "1_1") (pintype "passive"))
    )
    (net (code "55") (name "Net-(C107-Pad2)") (class "Default")
      (node (ref "C107") (pin "2") (pinfunction "2_2") (pintype "passive"))
      (node (ref "C44") (pin "2") (pinfunction "2_2") (pintype "passive"))
      (node (ref "R113") (pin "1") (pinfunction "1_1") (pintype "passive"))
    )
    (net (code "56") (name "Net-(IC2-IOUT-Pad80)") (class "Default")
      (node (ref "IC2") (pin "80") (pinfunction "IOUT_80") (pintype "output"))
      (node (ref "R56") (pin "1") (pinfunction "1_1") (pintype "passive"))
    )
    (net (code "57") (name "Net-(IC2-IOUT-Pad81)") (class "Default")
      (node (ref "IC2") (pin "81") (pinfunction "IOUT_81") (pintype "output"))
      (node (ref "R78") (pin "1") (pinfunction "1_1") (pintype "passive"))
    )
    (net (code "58") (name "Net-(IC2-XTAL_SEL)") (class "Default")
      (node (ref "IC2") (pin "95") (pinfunction "XTAL_SEL_95") (pintype "input"))
      (node (ref "R88") (pin "2") (pinfunction "2_2") (pintype "passive"))
    )
    (net (code "59") (name "Net-(IC13-CLKMODESEL)") (class "Default")
      (node (ref "IC13") (pin "32") (pinfunction "CLKMODESEL_32") (pintype "input"))
      (node (ref "R93") (pin "1") (pinfunction "1_1") (pintype "passive"))
      (node (ref "R94") (pin "2") (pinfunction "2_2") (pintype "passive"))
    )
    (net (code "60") (name "Net-(R90-Pad1)") (class "Default")
      (node (ref "R90") (pin "1") (pinfunction "1_1") (pintype "passive"))
      (node (ref "R92") (pin "2") (pinfunction "2_2") (pintype "passive"))
    )
    (net (code "61") (name "Net-(R113-Pad2)") (class "Default")
      (node (ref "R113") (pin "2") (pinfunction "2_2") (pintype "passive"))
      (node (ref "R140") (pin "1") (pinfunction "1_1") (pintype "passive"))
    )
    (net (code "62") (name "P1V8A") (class "Default")
      (node (ref "L16") (pin "2") (pinfunction "2_2") (pintype "passive"))
      (node (ref "L17") (pin "2") (pinfunction "2_2") (pintype "passive"))
      (node (ref "L19") (pin "2") (pinfunction "2_2") (pintype "passive"))
      (node (ref "L20") (pin "2") (pinfunction "2_2") (pintype "passive"))
      (node (ref "L21") (pin "2") (pinfunction "2_2") (pintype "passive"))
      (node (ref "L22") (pin "2") (pinfunction "2_2") (pintype "passive"))
    )
    (net (code "63") (name "P3V3A") (class "Default")
      (node (ref "L15") (pin "2") (pinfunction "2_2") (pintype "passive"))
      (node (ref "L18") (pin "2") (pinfunction "2_2") (pintype "passive"))
    )
    (net (code "64") (name "unconnected-(IC2-NC-Pad1)") (class "Default")
      (node (ref "IC2") (pin "1") (pinfunction "NC_1") (pintype "passive+no_connect"))
    )
    (net (code "65") (name "unconnected-(IC2-NC-Pad20)") (class "Default")
      (node (ref "IC2") (pin "20") (pinfunction "NC_20") (pintype "passive+no_connect"))
    )
    (net (code "66") (name "unconnected-(IC2-NC-Pad72)") (class "Default")
      (node (ref "IC2") (pin "72") (pinfunction "NC_72") (pintype "passive+no_connect"))
    )
    (net (code "67") (name "unconnected-(IC2-NC-Pad86)") (class "Default")
      (node (ref "IC2") (pin "86") (pinfunction "NC_86") (pintype "passive+no_connect"))
    )
    (net (code "68") (name "unconnected-(IC2-NC-Pad87)") (class "Default")
      (node (ref "IC2") (pin "87") (pinfunction "NC_87") (pintype "passive+no_connect"))
    )
    (net (code "69") (name "unconnected-(IC2-NC-Pad93)") (class "Default")
      (node (ref "IC2") (pin "93") (pinfunction "NC_93") (pintype "passive+no_connect"))
    )
    (net (code "70") (name "unconnected-(IC2-NC-Pad97)") (class "Default")
      (node (ref "IC2") (pin "97") (pinfunction "NC_97") (pintype "passive+no_connect"))
    )
    (net (code "71") (name "unconnected-(IC2-NC-Pad98)") (class "Default")
      (node (ref "IC2") (pin "98") (pinfunction "NC_98") (pintype "passive+no_connect"))
    )
    (net (code "72") (name "unconnected-(IC2-NC-Pad99)") (class "Default")
      (node (ref "IC2") (pin "99") (pinfunction "NC_99") (pintype "passive+no_connect"))
    )
    (net (code "73") (name "unconnected-(IC2-NC-Pad100)") (class "Default")
      (node (ref "IC2") (pin "100") (pinfunction "NC_100") (pintype "passive+no_connect"))
    )
    (net (code "74") (name "unconnected-(IC2-PDCLK-Pad40)") (class "Default")
      (node (ref "IC2") (pin "40") (pinfunction "PDCLK_40") (pintype "output+no_connect"))
    )
    (net (code "75") (name "unconnected-(IC2-RAM_SWP_OVR-Pad24)") (class "Default")
      (node (ref "IC2") (pin "24") (pinfunction "RAM_SWP_OVR_24") (pintype "output+no_connect"))
    )
    (net (code "76") (name "unconnected-(IC2-REFCLK_OUT-Pad94)") (class "Default")
      (node (ref "IC2") (pin "94") (pinfunction "REFCLK_OUT_94") (pintype "output+no_connect"))
    )
    (net (code "77") (name "unconnected-(IC13-FDBK_IN-Pad41)") (class "Default")
      (node (ref "IC13") (pin "41") (pinfunction "FDBK_IN_41") (pintype "input+no_connect"))
    )
    (net (code "78") (name "unconnected-(IC13-FDBK_INB-Pad40)") (class "Default")
      (node (ref "IC13") (pin "40") (pinfunction "FDBK_INB_40") (pintype "input+no_connect"))
    )
    (net (code "79") (name "unconnected-(IC13-NC-Pad12)") (class "Default")
      (node (ref "IC13") (pin "12") (pinfunction "NC_12") (pintype "passive+no_connect"))
    )
    (net (code "80") (name "unconnected-(IC13-NC-Pad13)") (class "Default")
      (node (ref "IC13") (pin "13") (pinfunction "NC_13") (pintype "passive+no_connect"))
    )
    (net (code "81") (name "unconnected-(IC13-NC-Pad15)") (class "Default")
      (node (ref "IC13") (pin "15") (pinfunction "NC_15") (pintype "passive+no_connect"))
    )
    (net (code "82") (name "unconnected-(IC13-NC-Pad16)") (class "Default")
      (node (ref "IC13") (pin "16") (pinfunction "NC_16") (pintype "passive+no_connect"))
    )
    (net (code "83") (name "unconnected-(IC13-NC-Pad17)") (class "Default")
      (node (ref "IC13") (pin "17") (pinfunction "NC_17") (pintype "passive+no_connect"))
    )
    (net (code "84") (name "unconnected-(IC13-NC-Pad18)") (class "Default")
      (node (ref "IC13") (pin "18") (pinfunction "NC_18") (pintype "passive+no_connect"))
    )
    (net (code "85") (name "unconnected-(IC13-NC-Pad20)") (class "Default")
      (node (ref "IC13") (pin "20") (pinfunction "NC_20") (pintype "passive+no_connect"))
    )
    (net (code "86") (name "unconnected-(IC13-NC-Pad21)") (class "Default")
      (node (ref "IC13") (pin "21") (pinfunction "NC_21") (pintype "passive+no_connect"))
    )
    (net (code "87") (name "unconnected-(IC13-NC-Pad22)") (class "Default")
      (node (ref "IC13") (pin "22") (pinfunction "NC_22") (pintype "passive+no_connect"))
    )
    (net (code "88") (name "unconnected-(IC13-OUT-Pad35)") (class "Default")
      (node (ref "IC13") (pin "35") (pinfunction "OUT_35") (pintype "output+no_connect"))
    )
    (net (code "89") (name "unconnected-(IC13-OUTB-Pad34)") (class "Default")
      (node (ref "IC13") (pin "34") (pinfunction "OUTB_34") (pintype "output+no_connect"))
    )
    (net (code "90") (name "unconnected-(IC13-OUT_CMOS-Pad38)") (class "Default")
      (node (ref "IC13") (pin "38") (pinfunction "OUT_CMOS_38") (pintype "output+no_connect"))
    )
  )
)
